# USB.net
KiCad netlist of a schematic drawn in Altium Designer
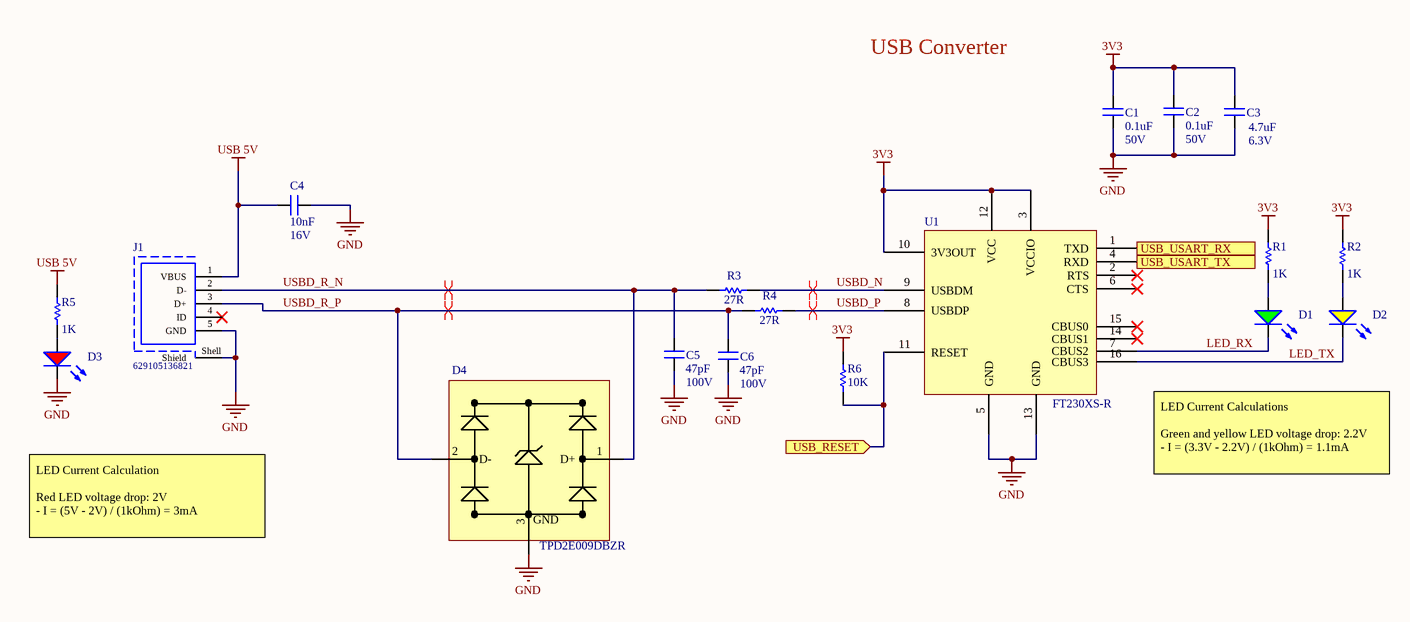
[diagram p0: USB.SchDoc]

(export (version "E")
  (design (tool "Eeschema 10.0.6"))
  (components
    (comp (ref "C1")
      (value "0.1uF")
      (footprint "CAPC2012X140N")
      (description "CAP CER 0.1UF 50V X7R 0805")
      (fields
        (field (name "TOLERANCE") "10%")
        (field (name "VOLTAGE RATING") "50V")
        (field (name "Comment") "CAP_0.1uF_50V_0805")
      )
      (libsource (lib "UWRT_Schematic_Library_2020") (part "CAP_0.1uF_50V_0805"))
    )
    (comp (ref "C2")
      (value "0.1uF")
      (footprint "CAPC2012X140N")
      (description "CAP CER 0.1UF 50V X7R 0805")
      (fields
        (field (name "TOLERANCE") "10%")
        (field (name "VOLTAGE RATING") "50V")
        (field (name "Comment") "CAP_0.1uF_50V_0805")
      )
      (libsource (lib "UWRT_Schematic_Library_2020") (part "CAP_0.1uF_50V_0805"))
    )
    (comp (ref "C3")
      (value "4.7uF")
      (footprint "CAPC0603(1608)55_N")
      (description "CAP CER 4.7UF 6.3V X5R 0603")
      (fields (field (name "VOLTAGE RATING") "6.3V") (field (name "Comment") "CAP_4.7uF_0603"))
      (libsource (lib "UWRT_Schematic_Library_2020") (part "CAP_4.7uF_0603"))
    )
    (comp (ref "C4")
      (value "10nF")
      (footprint "CAPC0603(1608)55_N")
      (description "CAP CER 10000PF 16V X7R 0603")
      (fields (field (name "VOLTAGE RATING") "16V") (field (name "Comment") "CAP_10nF_0603"))
      (libsource (lib "UWRT_Schematic_Library_2020") (part "CAP_10nF_0603"))
    )
    (comp (ref "C5")
      (value "47pF")
      (footprint "CAPC1608X87N")
      (description "CAP CER 47PF 100V C0G/NP0 0603")
      (fields (field (name "VOLTAGE RATING") "100V") (field (name "Comment") "CAP_47pF_100V_0603"))
      (libsource (lib "UWRT_Schematic_Library_2020") (part "CAP_47pF_100V_0603"))
    )
    (comp (ref "C6")
      (value "47pF")
      (footprint "CAPC1608X87N")
      (description "CAP CER 47PF 100V C0G/NP0 0603")
      (fields (field (name "VOLTAGE RATING") "100V") (field (name "Comment") "CAP_47pF_100V_0603"))
      (libsource (lib "UWRT_Schematic_Library_2020") (part "CAP_47pF_100V_0603"))
    )
    (comp (ref "D1")
      (value "DIO_LED_G")
      (footprint "LED_0805_LINE")
      (description "LED GREEN DIFFUSED 0805 SMD")
      (libsource (lib "UWRT_Schematic_Library_2020") (part "DIO_LED_G"))
    )
    (comp (ref "D2")
      (value "DIO_LED_Y")
      (footprint "LED_0805_LINE")
      (description "LED YELLOW DIFFUSED 0805 SMD")
      (libsource (lib "UWRT_Schematic_Library_2020") (part "DIO_LED_Y"))
    )
    (comp (ref "D3")
      (value "DIO_LED_R")
      (footprint "LED_0805_LINE")
      (description "LED RED DIFFUSED 0805 SMD")
      (libsource (lib "UWRT_Schematic_Library_2020") (part "DIO_LED_R"))
    )
    (comp (ref "D4")
      (value "TVS_DIODE_USB_5.5V")
      (footprint "SOT23-3")
      (description "ESD Suppressor Diode Arrays 8KV 3-Pin SOT-23 T/R")
      (fields
        (field (name "MANUFACTURER") "Texas Instruments")
        (field (name "MANUFACTURER PART NUMBER") "TPD2E009DBZR")
      )
      (libsource (lib "UWRT_Schematic_Library_2020") (part "TVS_DIODE_USB_5.5V"))
    )
    (comp (ref "J1")
      (value "629105136821")
      (footprint "629105136821")
      (description "Micro USB 2.0 Type B Receptacle WR-COM, Horizontal, SMT, with Pads and Pegs")
      (fields (field (name "MANUFACTURER") "Wurth Elektronik") (field (name "PUBLISHER") "WurthElektronik"))
      (libsource (lib "UWRT_Schematic_Library_2020") (part "WE 629105136821"))
    )
    (comp (ref "R1")
      (value "1K")
      (footprint "RESC0603(1608)_N")
      (description "RES SMD 1K OHM 5% 1/10W 0603")
      (fields (field (name "TOLERANCE") "5%") (field (name "Comment") "RES_1K_0603"))
      (libsource (lib "UWRT_Schematic_Library_2020") (part "RES_1K_0603"))
    )
    (comp (ref "R2")
      (value "1K")
      (footprint "RESC0603(1608)_N")
      (description "RES SMD 1K OHM 5% 1/10W 0603")
      (fields (field (name "TOLERANCE") "5%") (field (name "Comment") "RES_1K_0603"))
      (libsource (lib "UWRT_Schematic_Library_2020") (part "RES_1K_0603"))
    )
    (comp (ref "R3")
      (value "RES_27R_0603")
      (footprint "RESC0603(1608)_N")
      (description "RES SMD 27 OHM 5% 1/10W 0603")
      (fields
        (field (name "MANUFACTURER") "Yageo")
        (field (name "MANUFACTURER PART NUMBER") "RC0603JR-0727RL")
        (field (name "RESISTANCE") "27R")
      )
      (libsource (lib "UWRT_Schematic_Library_2020") (part "RES_27R_0603"))
    )
    (comp (ref "R4")
      (value "RES_27R_0603")
      (footprint "RESC0603(1608)_N")
      (description "RES SMD 27 OHM 5% 1/10W 0603")
      (fields
        (field (name "MANUFACTURER") "Yageo")
        (field (name "MANUFACTURER PART NUMBER") "RC0603JR-0727RL")
        (field (name "RESISTANCE") "27R")
      )
      (libsource (lib "UWRT_Schematic_Library_2020") (part "RES_27R_0603"))
    )
    (comp (ref "R5")
      (value "1K")
      (footprint "RESC0603(1608)_N")
      (description "RES SMD 1K OHM 5% 1/10W 0603")
      (fields (field (name "TOLERANCE") "5%") (field (name "Comment") "RES_1K_0603"))
      (libsource (lib "UWRT_Schematic_Library_2020") (part "RES_1K_0603"))
    )
    (comp (ref "R6")
      (value "10K")
      (footprint "RESC0603(1608)_N")
      (description "RES SMD 10K OHM 5% 1/10W 0603")
      (fields (field (name "TOLERANCE") "5%") (field (name "Comment") "RES_10K_0603"))
      (libsource (lib "UWRT_Schematic_Library_2020") (part "RES_10K_0603"))
    )
    (comp (ref "U1")
      (value "IC_USB_TRANSCEIVER")
      (footprint "SSOP16-0.635-5X4MM")
      (fields (field (name "MANUFACTURER PART NUMBER 1") "FT230XS-R"))
      (libsource (lib "UWRT_Schematic_Library_2020") (part "IC_USB_TRANSCEIVER"))
    )
  )
  (nets
    (net (code "1") (name "/LED_RX") (class "Default")
      (node (ref "D1") (pin "2") (pinfunction "K_2") (pintype "passive"))
      (node (ref "U1") (pin "7") (pinfunction "CBUS2_7") (pintype "passive"))
    )
    (net (code "2") (name "/LED_TX") (class "Default")
      (node (ref "D2") (pin "2") (pinfunction "K_2") (pintype "passive"))
      (node (ref "U1") (pin "16") (pinfunction "CBUS3_16") (pintype "passive"))
    )
    (net (code "3") (name "/USBD_N") (class "Default")
      (node (ref "R3") (pin "2") (pinfunction "2_2") (pintype "passive"))
      (node (ref "U1") (pin "9") (pinfunction "USBDM_9") (pintype "passive"))
    )
    (net (code "4") (name "/USBD_P") (class "Default")
      (node (ref "R4") (pin "2") (pinfunction "2_2") (pintype "passive"))
      (node (ref "U1") (pin "8") (pinfunction "USBDP_8") (pintype "passive"))
    )
    (net (code "5") (name "/USBD_R_N") (class "Default")
      (node (ref "C5") (pin "2") (pinfunction "2_2") (pintype "passive"))
      (node (ref "D4") (pin "1") (pinfunction "D+_1") (pintype "passive"))
      (node (ref "J1") (pin "2") (pinfunction "D-_2") (pintype "passive"))
      (node (ref "R3") (pin "1") (pinfunction "1_1") (pintype "passive"))
    )
    (net (code "6") (name "/USBD_R_P") (class "Default")
      (node (ref "C6") (pin "1") (pinfunction "1_1") (pintype "passive"))
      (node (ref "D4") (pin "2") (pinfunction "D-_2") (pintype "passive"))
      (node (ref "J1") (pin "3") (pinfunction "D+_3") (pintype "passive"))
      (node (ref "R4") (pin "1") (pinfunction "1_1") (pintype "passive"))
    )
    (net (code "7") (name "/USB_RESET") (class "Default")
      (node (ref "R6") (pin "1") (pinfunction "1_1") (pintype "passive"))
      (node (ref "U1") (pin "11") (pinfunction "RESET_11") (pintype "passive"))
    )
    (net (code "8") (name "/USB_USART_RX") (class "Default")
      (node (ref "U1") (pin "1") (pinfunction "TXD_1") (pintype "passive"))
    )
    (net (code "9") (name "/USB_USART_TX") (class "Default")
      (node (ref "U1") (pin "4") (pinfunction "RXD_4") (pintype "passive"))
    )
    (net (code "10") (name "3V3") (class "Default")
      (node (ref "C1") (pin "2") (pinfunction "2_2") (pintype "passive"))
      (node (ref "C2") (pin "2") (pinfunction "2_2") (pintype "passive"))
      (node (ref "C3") (pin "1") (pinfunction "1_1") (pintype "passive"))
      (node (ref "R1") (pin "2") (pinfunction "2_2") (pintype "passive"))
      (node (ref "R2") (pin "2") (pinfunction "2_2") (pintype "passive"))
      (node (ref "R6") (pin "2") (pinfunction "2_2") (pintype "passive"))
      (node (ref "U1") (pin "10") (pinfunction "3V3OUT_10") (pintype "passive"))
      (node (ref "U1") (pin "12") (pinfunction "VCC_12") (pintype "passive"))
      (node (ref "U1") (pin "3") (pinfunction "VCCIO_3") (pintype "passive"))
    )
    (net (code "11") (name "GND") (class "Default")
      (node (ref "C1") (pin "1") (pinfunction "1_1") (pintype "passive"))
      (node (ref "C2") (pin "1") (pinfunction "1_1") (pintype "passive"))
      (node (ref "C3") (pin "2") (pinfunction "2_2") (pintype "passive"))
      (node (ref "C4") (pin "2") (pinfunction "2_2") (pintype "passive"))
      (node (ref "C5") (pin "1") (pinfunction "1_1") (pintype "passive"))
      (node (ref "C6") (pin "2") (pinfunction "2_2") (pintype "passive"))
      (node (ref "D3") (pin "2") (pinfunction "K_2") (pintype "passive"))
      (node (ref "D4") (pin "3") (pinfunction "GND_3") (pintype "passive"))
      (node (ref "J1") (pin "5") (pinfunction "GND_5") (pintype "passive"))
      (node (ref "J1") (pin "Shell") (pinfunction "Shield_Shell") (pintype "passive"))
      (node (ref "U1") (pin "13") (pinfunction "GND_13") (pintype "passive"))
      (node (ref "U1") (pin "5") (pinfunction "GND_5") (pintype "passive"))
    )
    (net (code "12") (name "Net-(D1-A)") (class "Default")
      (node (ref "D1") (pin "1") (pinfunction "A_1") (pintype "passive"))
      (node (ref "R1") (pin "1") (pinfunction "1_1") (pintype "passive"))
    )
    (net (code "13") (name "Net-(D2-A)") (class "Default")
      (node (ref "D2") (pin "1") (pinfunction "A_1") (pintype "passive"))
      (node (ref "R2") (pin "1") (pinfunction "1_1") (pintype "passive"))
    )
    (net (code "14") (name "Net-(D3-A)") (class "Default")
      (node (ref "D3") (pin "1") (pinfunction "A_1") (pintype "passive"))
      (node (ref "R5") (pin "1") (pinfunction "1_1") (pintype "passive"))
    )
    (net (code "15") (name "USB 5V") (class "Default")
      (node (ref "C4") (pin "1") (pinfunction "1_1") (pintype "passive"))
      (node (ref "J1") (pin "1") (pinfunction "VBUS_1") (pintype "passive"))
      (node (ref "R5") (pin "2") (pinfunction "2_2") (pintype "passive"))
    )
    (net (code "16") (name "unconnected-(J1-ID-Pad4)") (class "Default")
      (node (ref "J1") (pin "4") (pinfunction "ID_4") (pintype "passive+no_connect"))
    )
    (net (code "17") (name "unconnected-(U1-CBUS0-Pad15)") (class "Default")
      (node (ref "U1") (pin "15") (pinfunction "CBUS0_15") (pintype "passive+no_connect"))
    )
    (net (code "18") (name "unconnected-(U1-CBUS1-Pad14)") (class "Default")
      (node (ref "U1") (pin "14") (pinfunction "CBUS1_14") (pintype "passive+no_connect"))
    )
    (net (code "19") (name "unconnected-(U1-CTS-Pad6)") (class "Default")
      (node (ref "U1") (pin "6") (pinfunction "CTS_6") (pintype "passive+no_connect"))
    )
    (net (code "20") (name "unconnected-(U1-RTS-Pad2)") (class "Default")
      (node (ref "U1") (pin "2") (pinfunction "RTS_2") (pintype "passive+no_connect"))
    )
  )
)
